# ext-memory.net
KiCad netlist of a schematic drawn in Altium Designer
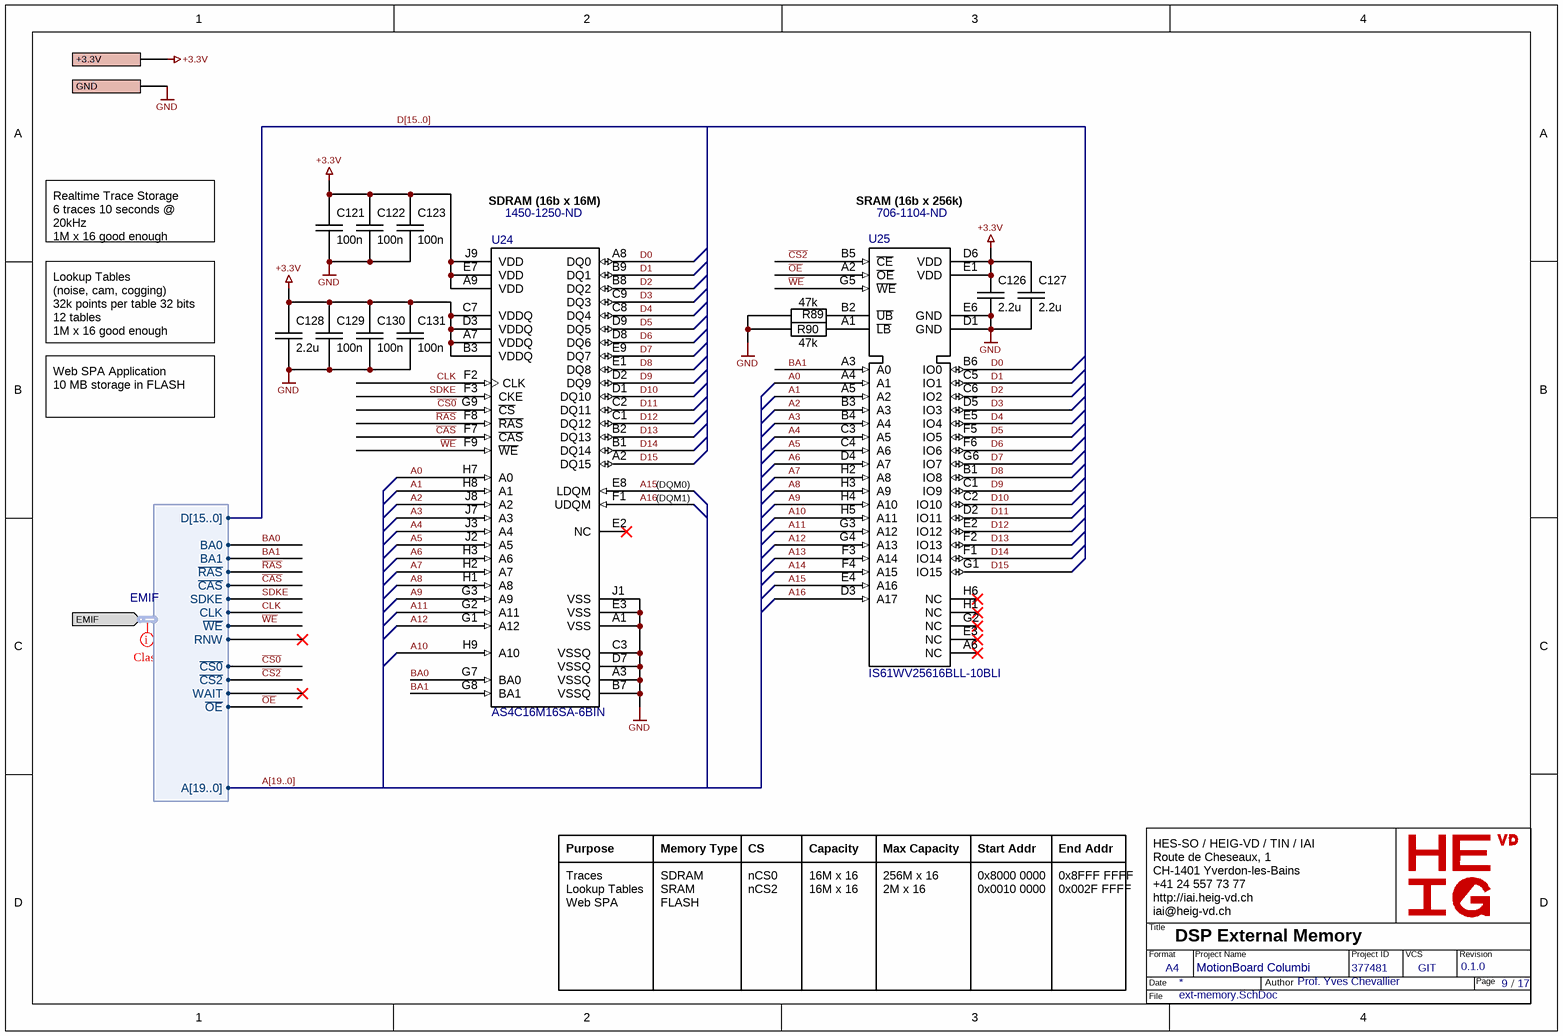
[diagram p0: ext-memory.SchDoc]

(export (version "E")
  (design (tool "Eeschema 10.0.6"))
  (components
    (comp (ref "C121")
      (value "100n")
      (footprint "SM/C0201")
      (description "Chip Capacitor")
      (fields (field (name "VOLTAGE") "16V") (field (name "Comment") "CL05A104KP5NNNC"))
      (libsource (lib "kalios") (part "C"))
    )
    (comp (ref "C122")
      (value "100n")
      (footprint "SM/C0201")
      (description "Chip Capacitor")
      (fields (field (name "VOLTAGE") "16V") (field (name "Comment") "CL05A104KP5NNNC"))
      (libsource (lib "kalios") (part "C"))
    )
    (comp (ref "C123")
      (value "100n")
      (footprint "SM/C0201")
      (description "Chip Capacitor")
      (fields (field (name "VOLTAGE") "16V") (field (name "Comment") "CL05A104KP5NNNC"))
      (libsource (lib "kalios") (part "C"))
    )
    (comp (ref "C126")
      (value "2.2u")
      (footprint "SM/C0402")
      (description "CAP CER 10UF 10V X5R 0805")
      (fields (field (name "VOLTAGE") "6.3V") (field (name "Comment") "CL05A225MQ5NNNC"))
      (libsource (lib "kalios") (part "C"))
    )
    (comp (ref "C127")
      (value "2.2u")
      (footprint "SM/C0402")
      (description "CAP CER 10UF 10V X5R 0805")
      (fields (field (name "VOLTAGE") "6.3V") (field (name "Comment") "CL05A225MQ5NNNC"))
      (libsource (lib "kalios") (part "C"))
    )
    (comp (ref "C128")
      (value "2.2u")
      (footprint "SM/C0402")
      (description "GRM155R61C225KE11D")
      (fields (field (name "VOLTAGE") "16V"))
      (libsource (lib "kalios") (part "C"))
    )
    (comp (ref "C129")
      (value "100n")
      (footprint "SM/C0201")
      (description "Chip Capacitor")
      (fields (field (name "VOLTAGE") "16V") (field (name "Comment") "CL05A104KP5NNNC"))
      (libsource (lib "kalios") (part "C"))
    )
    (comp (ref "C130")
      (value "100n")
      (footprint "SM/C0201")
      (description "Chip Capacitor")
      (fields (field (name "VOLTAGE") "16V") (field (name "Comment") "CL05A104KP5NNNC"))
      (libsource (lib "kalios") (part "C"))
    )
    (comp (ref "C131")
      (value "100n")
      (footprint "SM/C0201")
      (description "Chip Capacitor")
      (fields (field (name "VOLTAGE") "16V") (field (name "Comment") "CL05A104KP5NNNC"))
      (libsource (lib "kalios") (part "C"))
    )
    (comp (ref "R89")
      (value "47k")
      (footprint "SM/R0402")
      (description "47 kOhms ±1% 0.063W, 1/16W Chip Resistor 0402 (1005 Metric) Moisture Resistant Thick Film")
      (libsource (lib "kalios") (part "R"))
    )
    (comp (ref "R90")
      (value "47k")
      (footprint "SM/R0402")
      (description "47 kOhms ±1% 0.063W, 1/16W Chip Resistor 0402 (1005 Metric) Moisture Resistant Thick Film")
      (libsource (lib "kalios") (part "R"))
    )
    (comp (ref "U24")
      (value "AS4C16M16SA-6BIN")
      (footprint "TFBGA-54")
      (fields (field (name "SUPPLIER PART NUMBER 1") "1450-1250-ND"))
      (libsource (lib "kalios") (part "AS4C16M16SA-6BIN"))
    )
    (comp (ref "U25")
      (value "IS61WV25616BLL-10BLI")
      (footprint "BGA48C75P8X6_800X600X120N")
      (description "SRAM - Asynchronous Memory IC 4Mb (256K x 16) Parallel 10 ns 48-TFBGA (6x8)")
      (fields (field (name "SUPPLIER PART NUMBER 1") "706-1104-ND"))
      (libsource (lib "kalios") (part "IS61WV25616BLL-10BLI"))
    )
  )
  (nets
    (net (code "5") (name "+3.3V") (class "Default")
      (node (ref "C121") (pin "1") (pintype "passive"))
      (node (ref "C122") (pin "1") (pintype "passive"))
      (node (ref "C123") (pin "1") (pintype "passive"))
      (node (ref "C126") (pin "1") (pintype "passive"))
      (node (ref "C127") (pin "1") (pintype "passive"))
      (node (ref "C128") (pin "1") (pintype "passive"))
      (node (ref "C129") (pin "1") (pintype "passive"))
      (node (ref "C130") (pin "1") (pintype "passive"))
      (node (ref "C131") (pin "1") (pintype "passive"))
      (node (ref "U24") (pin "A7") (pinfunction "VDDQ_A7") (pintype "power_in"))
      (node (ref "U24") (pin "A9") (pinfunction "VDD_A9") (pintype "power_in"))
      (node (ref "U24") (pin "B3") (pinfunction "VDDQ_B3") (pintype "power_in"))
      (node (ref "U24") (pin "C7") (pinfunction "VDDQ_C7") (pintype "power_in"))
      (node (ref "U24") (pin "D3") (pinfunction "VDDQ_D3") (pintype "power_in"))
      (node (ref "U24") (pin "E7") (pinfunction "VDD_E7") (pintype "power_in"))
      (node (ref "U24") (pin "J9") (pinfunction "VDD_J9") (pintype "power_in"))
      (node (ref "U25") (pin "D6") (pinfunction "VDD_D6") (pintype "power_in"))
      (node (ref "U25") (pin "E1") (pinfunction "VDD_E1") (pintype "power_in"))
    )
    (net (code "6") (name "/A0") (class "Default")
      (node (ref "U24") (pin "H7") (pinfunction "A0_H7") (pintype "input"))
      (node (ref "U25") (pin "A4") (pinfunction "A1_A4") (pintype "input"))
    )
    (net (code "7") (name "/A1") (class "Default")
      (node (ref "U24") (pin "H8") (pinfunction "A1_H8") (pintype "input"))
      (node (ref "U25") (pin "A5") (pinfunction "A2_A5") (pintype "input"))
    )
    (net (code "8") (name "/A2") (class "Default")
      (node (ref "U24") (pin "J8") (pinfunction "A2_J8") (pintype "input"))
      (node (ref "U25") (pin "B3") (pinfunction "A3_B3") (pintype "input"))
    )
    (net (code "9") (name "/A3") (class "Default")
      (node (ref "U24") (pin "J7") (pinfunction "A3_J7") (pintype "input"))
      (node (ref "U25") (pin "B4") (pinfunction "A4_B4") (pintype "input"))
    )
    (net (code "10") (name "/A4") (class "Default")
      (node (ref "U24") (pin "J3") (pinfunction "A4_J3") (pintype "input"))
      (node (ref "U25") (pin "C3") (pinfunction "A5_C3") (pintype "input"))
    )
    (net (code "11") (name "/A5") (class "Default")
      (node (ref "U24") (pin "J2") (pinfunction "A5_J2") (pintype "input"))
      (node (ref "U25") (pin "C4") (pinfunction "A6_C4") (pintype "input"))
    )
    (net (code "12") (name "/A6") (class "Default")
      (node (ref "U24") (pin "H3") (pinfunction "A6_H3") (pintype "input"))
      (node (ref "U25") (pin "D4") (pinfunction "A7_D4") (pintype "input"))
    )
    (net (code "13") (name "/A7") (class "Default")
      (node (ref "U24") (pin "H2") (pinfunction "A7_H2") (pintype "input"))
      (node (ref "U25") (pin "H2") (pinfunction "A8_H2") (pintype "input"))
    )
    (net (code "14") (name "/A8") (class "Default")
      (node (ref "U24") (pin "H1") (pinfunction "A8_H1") (pintype "input"))
      (node (ref "U25") (pin "H3") (pinfunction "A9_H3") (pintype "input"))
    )
    (net (code "15") (name "/A9") (class "Default")
      (node (ref "U24") (pin "G3") (pinfunction "A9_G3") (pintype "input"))
      (node (ref "U25") (pin "H4") (pinfunction "A10_H4") (pintype "input"))
    )
    (net (code "16") (name "/A10") (class "Default")
      (node (ref "U24") (pin "H9") (pinfunction "A10_H9") (pintype "input"))
      (node (ref "U25") (pin "H5") (pinfunction "A11_H5") (pintype "input"))
    )
    (net (code "17") (name "/A11") (class "Default")
      (node (ref "U24") (pin "G2") (pinfunction "A11_G2") (pintype "input"))
      (node (ref "U25") (pin "G3") (pinfunction "A12_G3") (pintype "input"))
    )
    (net (code "18") (name "/A12") (class "Default")
      (node (ref "U24") (pin "G1") (pinfunction "A12_G1") (pintype "input"))
      (node (ref "U25") (pin "G4") (pinfunction "A13_G4") (pintype "input"))
    )
    (net (code "19") (name "/A13") (class "Default")
      (node (ref "U25") (pin "F3") (pinfunction "A14_F3") (pintype "input"))
    )
    (net (code "20") (name "/A14") (class "Default")
      (node (ref "U25") (pin "F4") (pinfunction "A15_F4") (pintype "input"))
    )
    (net (code "21") (name "/A15") (class "Default")
      (node (ref "U24") (pin "E8") (pinfunction "LDQM_E8") (pintype "input"))
      (node (ref "U25") (pin "E4") (pinfunction "A16_E4") (pintype "input"))
    )
    (net (code "22") (name "/A16") (class "Default")
      (node (ref "U24") (pin "F1") (pinfunction "UDQM_F1") (pintype "input"))
      (node (ref "U25") (pin "D3") (pinfunction "A17_D3") (pintype "input"))
    )
    (net (code "24") (name "/BA0") (class "Default")
      (node (ref "U24") (pin "G7") (pinfunction "BA0_G7") (pintype "input"))
    )
    (net (code "25") (name "/BA1") (class "Default")
      (node (ref "U24") (pin "G8") (pinfunction "BA1_G8") (pintype "input"))
      (node (ref "U25") (pin "A3") (pinfunction "A0_A3") (pintype "input"))
    )
    (net (code "26") (name "/CLK") (class "Default")
      (node (ref "U24") (pin "F2") (pinfunction "CLK_F2") (pintype "input"))
    )
    (net (code "27") (name "/D0") (class "Default")
      (node (ref "U24") (pin "A8") (pinfunction "DQ0_A8") (pintype "bidirectional"))
      (node (ref "U25") (pin "B6") (pinfunction "IO0_B6") (pintype "bidirectional"))
    )
    (net (code "28") (name "/D1") (class "Default")
      (node (ref "U24") (pin "B9") (pinfunction "DQ1_B9") (pintype "bidirectional"))
      (node (ref "U25") (pin "C5") (pinfunction "IO1_C5") (pintype "bidirectional"))
    )
    (net (code "29") (name "/D2") (class "Default")
      (node (ref "U24") (pin "B8") (pinfunction "DQ2_B8") (pintype "bidirectional"))
      (node (ref "U25") (pin "C6") (pinfunction "IO2_C6") (pintype "bidirectional"))
    )
    (net (code "30") (name "/D3") (class "Default")
      (node (ref "U24") (pin "C9") (pinfunction "DQ3_C9") (pintype "bidirectional"))
      (node (ref "U25") (pin "D5") (pinfunction "IO3_D5") (pintype "bidirectional"))
    )
    (net (code "31") (name "/D4") (class "Default")
      (node (ref "U24") (pin "C8") (pinfunction "DQ4_C8") (pintype "bidirectional"))
      (node (ref "U25") (pin "E5") (pinfunction "IO4_E5") (pintype "bidirectional"))
    )
    (net (code "32") (name "/D5") (class "Default")
      (node (ref "U24") (pin "D9") (pinfunction "DQ5_D9") (pintype "bidirectional"))
      (node (ref "U25") (pin "F5") (pinfunction "IO5_F5") (pintype "bidirectional"))
    )
    (net (code "33") (name "/D6") (class "Default")
      (node (ref "U24") (pin "D8") (pinfunction "DQ6_D8") (pintype "bidirectional"))
      (node (ref "U25") (pin "F6") (pinfunction "IO6_F6") (pintype "bidirectional"))
    )
    (net (code "34") (name "/D7") (class "Default")
      (node (ref "U24") (pin "E9") (pinfunction "DQ7_E9") (pintype "bidirectional"))
      (node (ref "U25") (pin "G6") (pinfunction "IO7_G6") (pintype "bidirectional"))
    )
    (net (code "35") (name "/D8") (class "Default")
      (node (ref "U24") (pin "E1") (pinfunction "DQ8_E1") (pintype "bidirectional"))
      (node (ref "U25") (pin "B1") (pinfunction "IO8_B1") (pintype "bidirectional"))
    )
    (net (code "36") (name "/D9") (class "Default")
      (node (ref "U24") (pin "D2") (pinfunction "DQ9_D2") (pintype "bidirectional"))
      (node (ref "U25") (pin "C1") (pinfunction "IO9_C1") (pintype "bidirectional"))
    )
    (net (code "37") (name "/D10") (class "Default")
      (node (ref "U24") (pin "D1") (pinfunction "DQ10_D1") (pintype "bidirectional"))
      (node (ref "U25") (pin "C2") (pinfunction "IO10_C2") (pintype "bidirectional"))
    )
    (net (code "38") (name "/D11") (class "Default")
      (node (ref "U24") (pin "C2") (pinfunction "DQ11_C2") (pintype "bidirectional"))
      (node (ref "U25") (pin "D2") (pinfunction "IO11_D2") (pintype "bidirectional"))
    )
    (net (code "39") (name "/D12") (class "Default")
      (node (ref "U24") (pin "C1") (pinfunction "DQ12_C1") (pintype "bidirectional"))
      (node (ref "U25") (pin "E2") (pinfunction "IO12_E2") (pintype "bidirectional"))
    )
    (net (code "40") (name "/D13") (class "Default")
      (node (ref "U24") (pin "B2") (pinfunction "DQ13_B2") (pintype "bidirectional"))
      (node (ref "U25") (pin "F2") (pinfunction "IO13_F2") (pintype "bidirectional"))
    )
    (net (code "41") (name "/D14") (class "Default")
      (node (ref "U24") (pin "B1") (pinfunction "DQ14_B1") (pintype "bidirectional"))
      (node (ref "U25") (pin "F1") (pinfunction "IO14_F1") (pintype "bidirectional"))
    )
    (net (code "42") (name "/D15") (class "Default")
      (node (ref "U24") (pin "A2") (pinfunction "DQ15_A2") (pintype "bidirectional"))
      (node (ref "U25") (pin "G1") (pinfunction "IO15_G1") (pintype "bidirectional"))
    )
    (net (code "44") (name "/SDKE") (class "Default")
      (node (ref "U24") (pin "F3") (pinfunction "CKE_F3") (pintype "input"))
    )
    (net (code "46") (name "/~{CAS}") (class "Default")
      (node (ref "U24") (pin "F7") (pinfunction "~{CAS}_F7") (pintype "input"))
    )
    (net (code "47") (name "/~{CS0}") (class "Default")
      (node (ref "U24") (pin "G9") (pinfunction "~{CS}_G9") (pintype "input"))
    )
    (net (code "48") (name "/~{CS2}") (class "Default")
      (node (ref "U25") (pin "B5") (pinfunction "~{CE}_B5") (pintype "input"))
    )
    (net (code "49") (name "/~{OE}") (class "Default")
      (node (ref "U25") (pin "A2") (pinfunction "~{OE}_A2") (pintype "input"))
    )
    (net (code "50") (name "/~{RAS}") (class "Default")
      (node (ref "U24") (pin "F8") (pinfunction "~{RAS}_F8") (pintype "input"))
    )
    (net (code "51") (name "/~{WE}") (class "Default")
      (node (ref "U24") (pin "F9") (pinfunction "~{WE}_F9") (pintype "input"))
      (node (ref "U25") (pin "G5") (pinfunction "~{WE}_G5") (pintype "input"))
    )
    (net (code "52") (name "GND") (class "Default")
      (node (ref "C121") (pin "2") (pintype "passive"))
      (node (ref "C122") (pin "2") (pintype "passive"))
      (node (ref "C123") (pin "2") (pintype "passive"))
      (node (ref "C126") (pin "2") (pintype "passive"))
      (node (ref "C127") (pin "2") (pintype "passive"))
      (node (ref "C128") (pin "2") (pintype "passive"))
      (node (ref "C129") (pin "2") (pintype "passive"))
      (node (ref "C130") (pin "2") (pintype "passive"))
      (node (ref "C131") (pin "2") (pintype "passive"))
      (node (ref "R89") (pin "1") (pintype "passive"))
      (node (ref "R90") (pin "1") (pintype "passive"))
      (node (ref "U24") (pin "A1") (pinfunction "VSS_A1") (pintype "power_in"))
      (node (ref "U24") (pin "A3") (pinfunction "VSSQ_A3") (pintype "power_in"))
      (node (ref "U24") (pin "B7") (pinfunction "VSSQ_B7") (pintype "power_in"))
      (node (ref "U24") (pin "C3") (pinfunction "VSSQ_C3") (pintype "power_in"))
      (node (ref "U24") (pin "D7") (pinfunction "VSSQ_D7") (pintype "power_in"))
      (node (ref "U24") (pin "E3") (pinfunction "VSS_E3") (pintype "power_in"))
      (node (ref "U24") (pin "J1") (pinfunction "VSS_J1") (pintype "power_in"))
      (node (ref "U25") (pin "D1") (pinfunction "GND_D1") (pintype "power_in"))
      (node (ref "U25") (pin "E6") (pinfunction "GND_E6") (pintype "power_in"))
    )
    (net (code "53") (name "Net-(U25-~{LB})") (class "Default")
      (node (ref "R90") (pin "2") (pintype "passive"))
      (node (ref "U25") (pin "A1") (pinfunction "~{LB}_A1") (pintype "passive"))
    )
    (net (code "54") (name "Net-(U25-~{UB})") (class "Default")
      (node (ref "R89") (pin "2") (pintype "passive"))
      (node (ref "U25") (pin "B2") (pinfunction "~{UB}_B2") (pintype "passive"))
    )
    (net (code "55") (name "unconnected-(U24-NC-PadE2)") (class "Default")
      (node (ref "U24") (pin "E2") (pinfunction "NC_E2") (pintype "passive+no_connect"))
    )
    (net (code "56") (name "unconnected-(U25-NC-PadA6)") (class "Default")
      (node (ref "U25") (pin "A6") (pinfunction "NC_A6") (pintype "passive+no_connect"))
    )
    (net (code "57") (name "unconnected-(U25-NC-PadE3)") (class "Default")
      (node (ref "U25") (pin "E3") (pinfunction "NC_E3") (pintype "passive+no_connect"))
    )
    (net (code "58") (name "unconnected-(U25-NC-PadG2)") (class "Default")
      (node (ref "U25") (pin "G2") (pinfunction "NC_G2") (pintype "passive+no_connect"))
    )
    (net (code "59") (name "unconnected-(U25-NC-PadH1)") (class "Default")
      (node (ref "U25") (pin "H1") (pinfunction "NC_H1") (pintype "passive+no_connect"))
    )
    (net (code "60") (name "unconnected-(U25-NC-PadH6)") (class "Default")
      (node (ref "U25") (pin "H6") (pinfunction "NC_H6") (pintype "passive+no_connect"))
    )
  )
)
